# XBeePowerMod.net
KiCad netlist of a schematic drawn in EAGLE
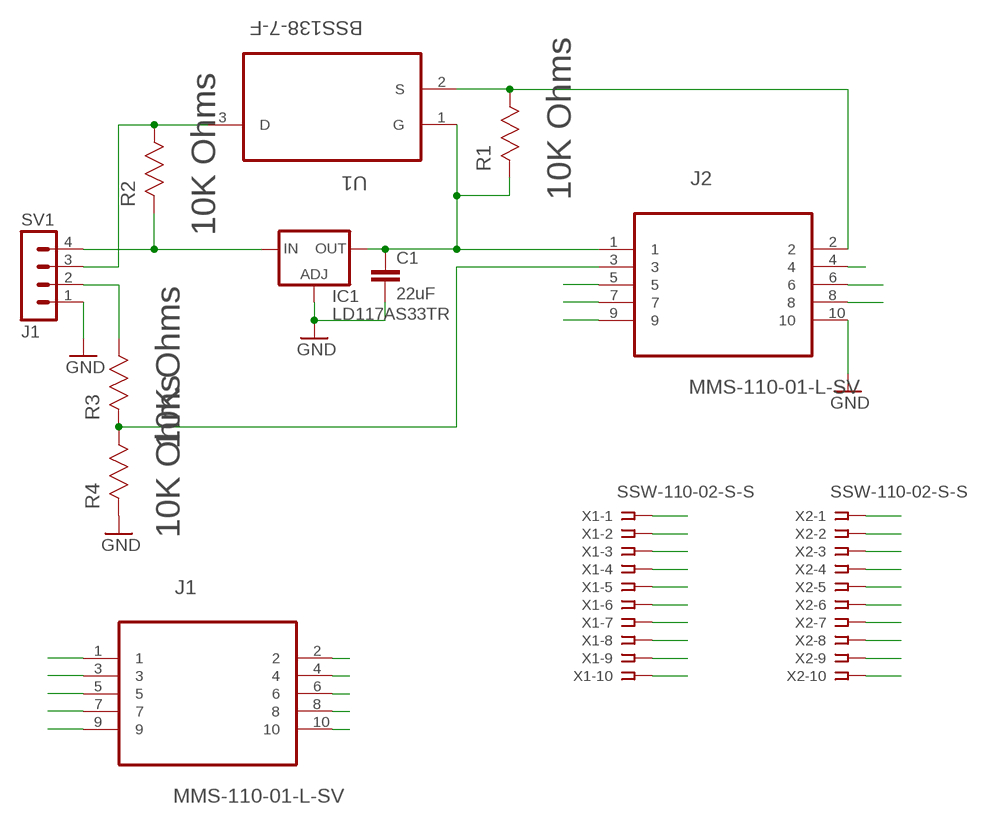
[diagram p0: schematic, sheet 1]

(export (version "E")
  (design (tool "Eeschema 10.0.6"))
  (components
    (comp (ref "C1")
      (value "22uF")
      (footprint "eagle-import:C1206K")
      (libsource (lib "eagle-import") (part "C-EUC1206K"))
    )
    (comp (ref "IC1")
      (value "LD117AS33TR")
      (footprint "eagle-import:SOT223")
      (libsource (lib "eagle-import") (part "LD117A?S33TR"))
    )
    (comp (ref "J1")
      (value "MMS-110-01-L-SV")
      (footprint "eagle-import:SAMTEC_MMS-110-01-L-SV")
      (libsource (lib "eagle-import") (part "MMS-110-01-L-SV"))
    )
    (comp (ref "J2")
      (value "MMS-110-01-L-SV")
      (footprint "eagle-import:SAMTEC_MMS-110-01-L-SV")
      (libsource (lib "eagle-import") (part "MMS-110-01-L-SV"))
    )
    (comp (ref "R1")
      (value "10K Ohms")
      (footprint "eagle-import:RESC3216X71N")
      (fields (field (name "MPN") "MC0.125W12061%10K") (field (name "TOLERANCE") "±1%"))
      (libsource (lib "eagle-import") (part "MC0.125W12061%10K"))
    )
    (comp (ref "R2")
      (value "10K Ohms")
      (footprint "eagle-import:RESC3216X71N")
      (fields (field (name "MPN") "MC0.125W12061%10K") (field (name "TOLERANCE") "±1%"))
      (libsource (lib "eagle-import") (part "MC0.125W12061%10K"))
    )
    (comp (ref "R3")
      (value "10K Ohms")
      (footprint "eagle-import:RESC3216X71N")
      (fields (field (name "MPN") "MC0.125W12061%10K") (field (name "TOLERANCE") "±1%"))
      (libsource (lib "eagle-import") (part "MC0.125W12061%10K"))
    )
    (comp (ref "R4")
      (value "10K Ohms")
      (footprint "eagle-import:RESC3216X71N")
      (fields (field (name "MPN") "MC0.125W12061%10K") (field (name "TOLERANCE") "±1%"))
      (libsource (lib "eagle-import") (part "MC0.125W12061%10K"))
    )
    (comp (ref "SV1")
      (value "J1")
      (footprint "eagle-import:MA04-1")
      (libsource (lib "eagle-import") (part "MA04-1"))
    )
    (comp (ref "U1")
      (value "BSS138-7-F")
      (footprint "eagle-import:SOT95P240X110-3N")
      (libsource (lib "eagle-import") (part "BSS138-7-F"))
    )
    (comp (ref "X1")
      (value "SSW-110-02-S-S")
      (footprint "eagle-import:SSW-110-02-S-S")
      (libsource (lib "eagle-import") (part "SSW-110-02-S-S"))
    )
    (comp (ref "X2")
      (value "SSW-110-02-S-S")
      (footprint "eagle-import:SSW-110-02-S-S")
      (libsource (lib "eagle-import") (part "SSW-110-02-S-S"))
    )
  )
  (nets
    (net (code "1") (name "/X10") (class "Default")
      (node (ref "J1") (pin "10") (pinfunction "10_10") (pintype "passive"))
      (node (ref "X1") (pin "10") (pinfunction "1_10") (pintype "passive"))
    )
    (net (code "2") (name "/X11") (class "Default")
      (node (ref "J1") (pin "1") (pinfunction "1_1") (pintype "passive"))
      (node (ref "X1") (pin "1") (pinfunction "1_1") (pintype "passive"))
    )
    (net (code "3") (name "/X12") (class "Default")
      (node (ref "J1") (pin "2") (pinfunction "2_2") (pintype "passive"))
      (node (ref "X1") (pin "2") (pinfunction "1_2") (pintype "passive"))
    )
    (net (code "4") (name "/X13") (class "Default")
      (node (ref "J1") (pin "3") (pinfunction "3_3") (pintype "passive"))
      (node (ref "X1") (pin "3") (pinfunction "1_3") (pintype "passive"))
    )
    (net (code "5") (name "/X14") (class "Default")
      (node (ref "J1") (pin "4") (pinfunction "4_4") (pintype "passive"))
      (node (ref "X1") (pin "4") (pinfunction "1_4") (pintype "passive"))
    )
    (net (code "6") (name "/X15") (class "Default")
      (node (ref "J1") (pin "5") (pinfunction "5_5") (pintype "passive"))
      (node (ref "X1") (pin "5") (pinfunction "1_5") (pintype "passive"))
    )
    (net (code "7") (name "/X16") (class "Default")
      (node (ref "J1") (pin "6") (pinfunction "6_6") (pintype "passive"))
      (node (ref "X1") (pin "6") (pinfunction "1_6") (pintype "passive"))
    )
    (net (code "8") (name "/X17") (class "Default")
      (node (ref "J1") (pin "7") (pinfunction "7_7") (pintype "passive"))
      (node (ref "X1") (pin "7") (pinfunction "1_7") (pintype "passive"))
    )
    (net (code "9") (name "/X18") (class "Default")
      (node (ref "J1") (pin "8") (pinfunction "8_8") (pintype "passive"))
      (node (ref "X1") (pin "8") (pinfunction "1_8") (pintype "passive"))
    )
    (net (code "10") (name "/X19") (class "Default")
      (node (ref "J1") (pin "9") (pinfunction "9_9") (pintype "passive"))
      (node (ref "X1") (pin "9") (pinfunction "1_9") (pintype "passive"))
    )
    (net (code "11") (name "/X21") (class "Default")
      (node (ref "C1") (pin "1") (pinfunction "1_1") (pintype "passive"))
      (node (ref "IC1") (pin "4") (pinfunction "OUT_4") (pintype "passive"))
      (node (ref "J2") (pin "1") (pinfunction "1_1") (pintype "passive"))
      (node (ref "R1") (pin "2") (pinfunction "R2_2") (pintype "passive"))
      (node (ref "U1") (pin "1") (pinfunction "G_1") (pintype "passive"))
      (node (ref "X2") (pin "1") (pinfunction "1_1") (pintype "passive"))
    )
    (net (code "12") (name "/X22") (class "Default")
      (node (ref "J2") (pin "2") (pinfunction "2_2") (pintype "passive"))
      (node (ref "R1") (pin "1") (pinfunction "R1_1") (pintype "passive"))
      (node (ref "U1") (pin "2") (pinfunction "S_2") (pintype "passive"))
      (node (ref "X2") (pin "2") (pinfunction "1_2") (pintype "passive"))
    )
    (net (code "13") (name "/X23") (class "Default")
      (node (ref "J2") (pin "3") (pinfunction "3_3") (pintype "passive"))
      (node (ref "R3") (pin "2") (pinfunction "R2_2") (pintype "passive"))
      (node (ref "R4") (pin "1") (pinfunction "R1_1") (pintype "passive"))
      (node (ref "X2") (pin "3") (pinfunction "1_3") (pintype "passive"))
    )
    (net (code "14") (name "/X24") (class "Default")
      (node (ref "J2") (pin "4") (pinfunction "4_4") (pintype "passive"))
      (node (ref "X2") (pin "4") (pinfunction "1_4") (pintype "passive"))
    )
    (net (code "15") (name "/X25") (class "Default")
      (node (ref "J2") (pin "5") (pinfunction "5_5") (pintype "passive"))
      (node (ref "X2") (pin "5") (pinfunction "1_5") (pintype "passive"))
    )
    (net (code "16") (name "/X26") (class "Default")
      (node (ref "J2") (pin "6") (pinfunction "6_6") (pintype "passive"))
      (node (ref "X2") (pin "6") (pinfunction "1_6") (pintype "passive"))
    )
    (net (code "17") (name "/X27") (class "Default")
      (node (ref "J2") (pin "7") (pinfunction "7_7") (pintype "passive"))
      (node (ref "X2") (pin "7") (pinfunction "1_7") (pintype "passive"))
    )
    (net (code "18") (name "/X28") (class "Default")
      (node (ref "J2") (pin "8") (pinfunction "8_8") (pintype "passive"))
      (node (ref "X2") (pin "8") (pinfunction "1_8") (pintype "passive"))
    )
    (net (code "19") (name "/X29") (class "Default")
      (node (ref "J2") (pin "9") (pinfunction "9_9") (pintype "passive"))
      (node (ref "X2") (pin "9") (pinfunction "1_9") (pintype "passive"))
    )
    (net (code "20") (name "GND") (class "Default")
      (node (ref "C1") (pin "2") (pinfunction "2_2") (pintype "passive"))
      (node (ref "IC1") (pin "1") (pinfunction "ADJ_1") (pintype "input"))
      (node (ref "J2") (pin "10") (pinfunction "10_10") (pintype "passive"))
      (node (ref "R4") (pin "2") (pinfunction "R2_2") (pintype "passive"))
      (node (ref "SV1") (pin "1") (pinfunction "1_1") (pintype "passive"))
      (node (ref "X2") (pin "10") (pinfunction "1_10") (pintype "passive"))
    )
    (net (code "21") (name "Net-(IC1-IN)") (class "Default")
      (node (ref "IC1") (pin "3") (pinfunction "IN_3") (pintype "input"))
      (node (ref "R2") (pin "2") (pinfunction "R2_2") (pintype "passive"))
      (node (ref "SV1") (pin "4") (pinfunction "4_4") (pintype "passive"))
    )
    (net (code "22") (name "Net-(R2-R1)") (class "Default")
      (node (ref "R2") (pin "1") (pinfunction "R1_1") (pintype "passive"))
      (node (ref "SV1") (pin "3") (pinfunction "3_3") (pintype "passive"))
      (node (ref "U1") (pin "3") (pinfunction "D_3") (pintype "passive"))
    )
    (net (code "23") (name "Net-(R3-R1)") (class "Default")
      (node (ref "R3") (pin "1") (pinfunction "R1_1") (pintype "passive"))
      (node (ref "SV1") (pin "2") (pinfunction "2_2") (pintype "passive"))
    )
  )
)
